# doch.net
KiCad netlist of a schematic drawn in EAGLE
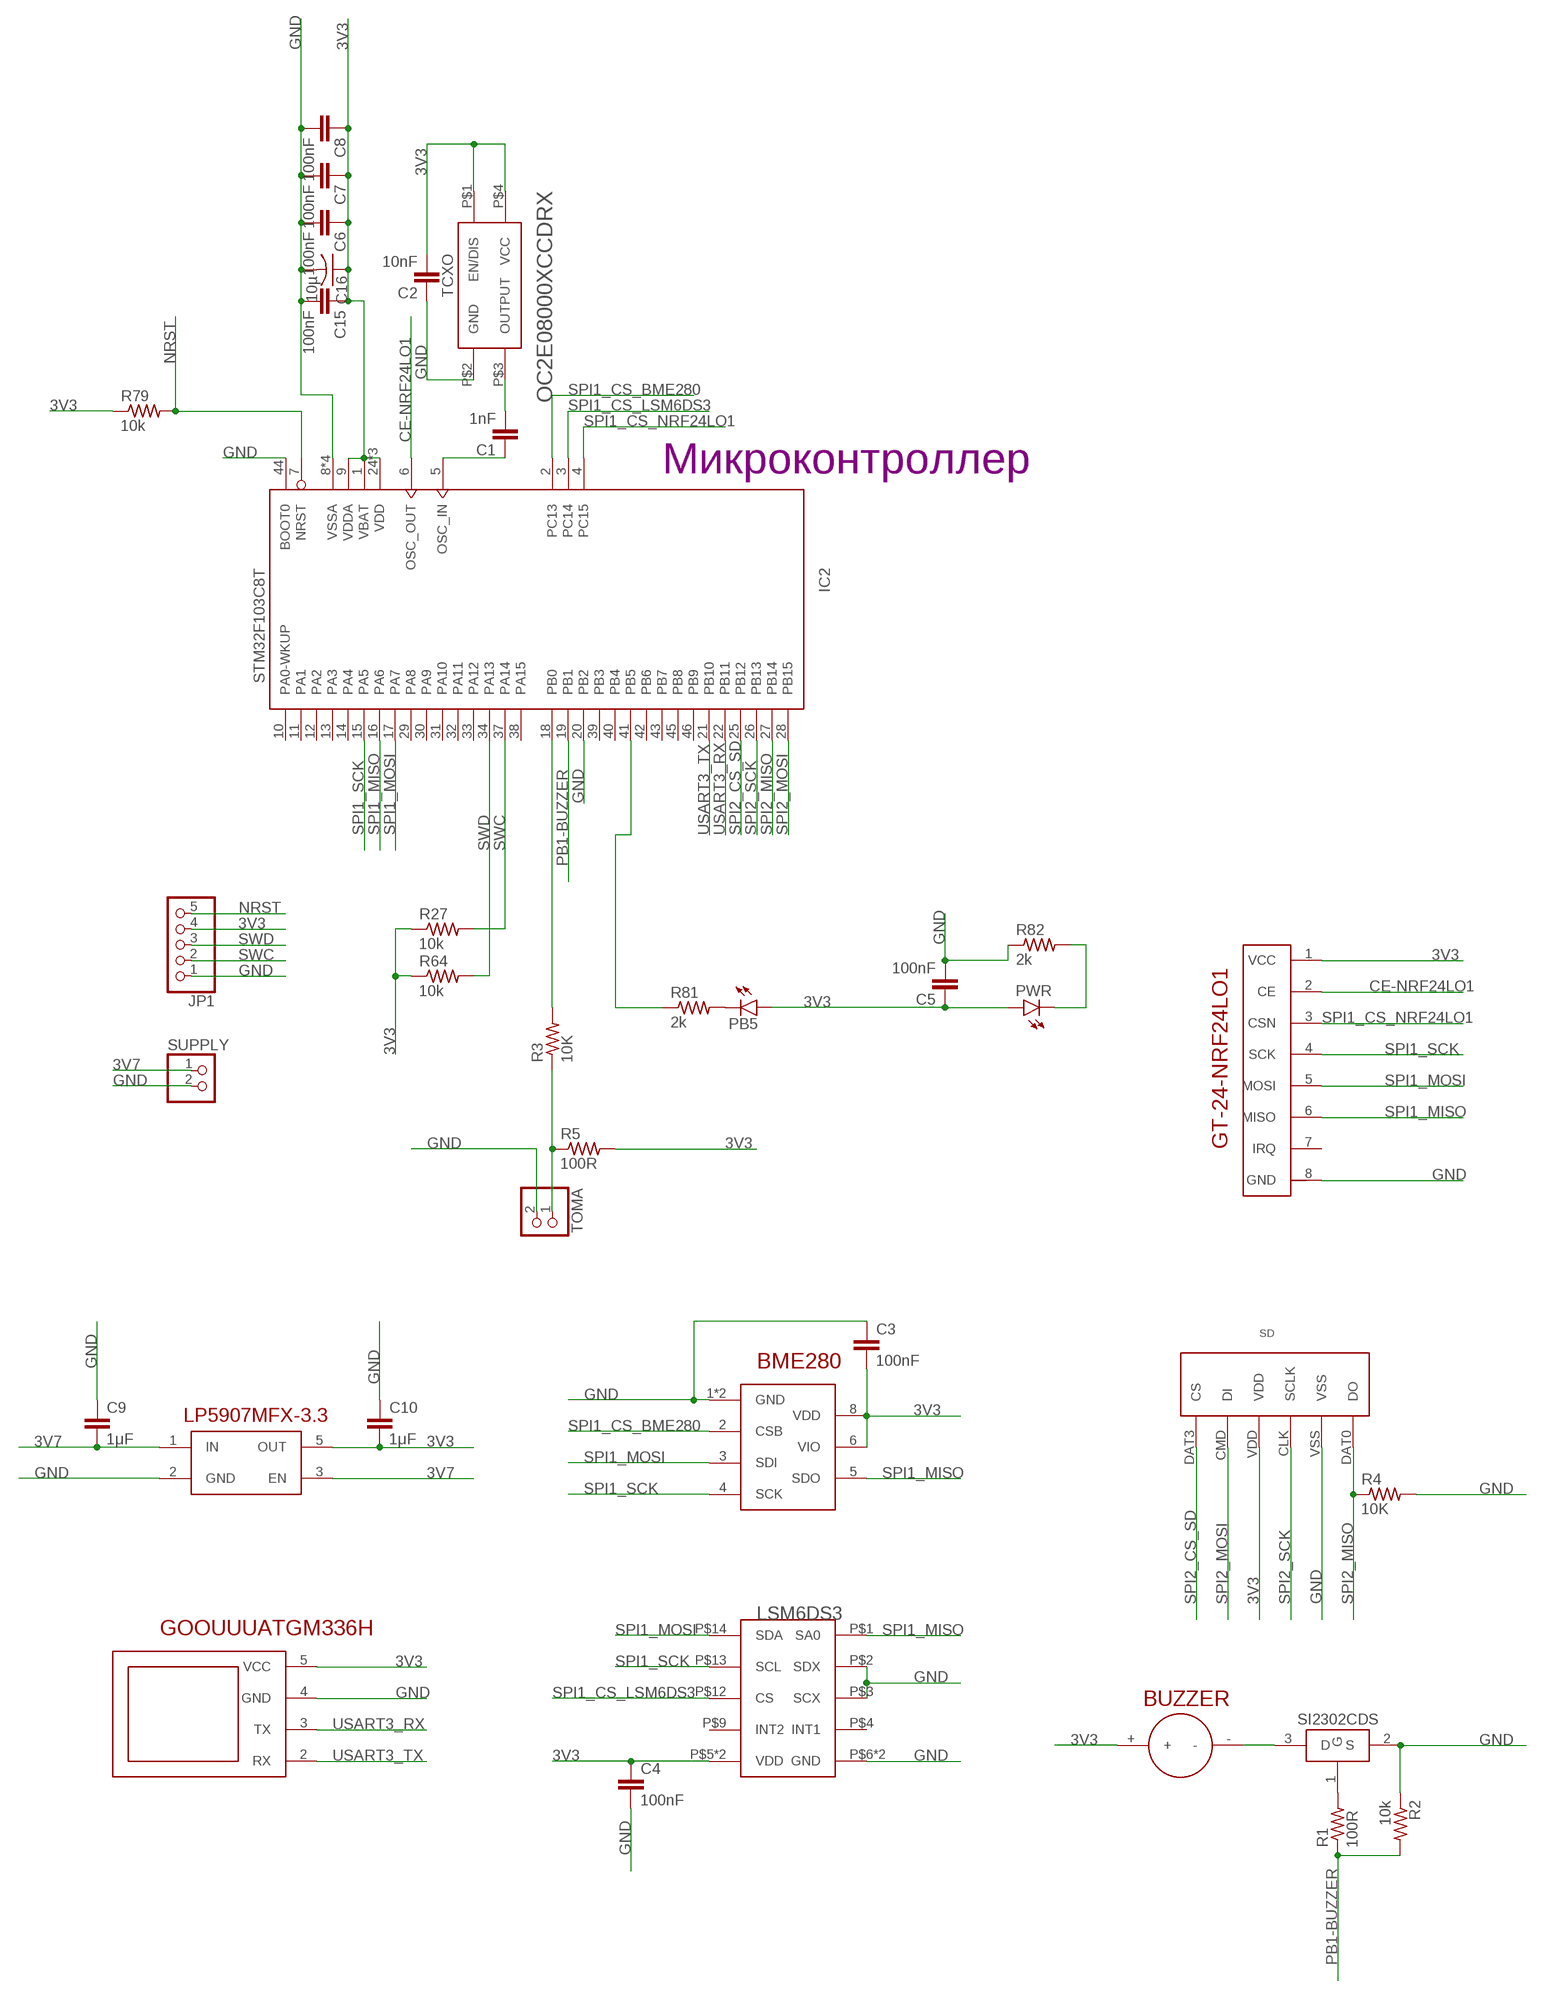
[diagram p0: schematic, sheet 1]

(export (version "E")
  (design (tool "Eeschema 10.0.6"))
  (components
    (comp (ref "BME280")
      (value "BME280CHIP")
      (footprint "eagle-import:BME280CHIP")
      (libsource (lib "eagle-import") (part "BME280CHIP"))
    )
    (comp (ref "BUZZER")
      (value "BUZZER")
      (footprint "eagle-import:BUZZER")
      (libsource (lib "eagle-import") (part "BUZZER"))
    )
    (comp (ref "C1")
      (value "1nF")
      (footprint "eagle-import:C0603")
      (libsource (lib "eagle-import") (part "C-EUC0603"))
    )
    (comp (ref "C2")
      (value "10nF")
      (footprint "eagle-import:C0603")
      (libsource (lib "eagle-import") (part "C-EUC0603"))
    )
    (comp (ref "C3")
      (value "100nF")
      (footprint "eagle-import:C0603")
      (libsource (lib "eagle-import") (part "C-EUC0603"))
    )
    (comp (ref "C4")
      (value "100nF")
      (footprint "eagle-import:C0603")
      (libsource (lib "eagle-import") (part "C-EUC0603"))
    )
    (comp (ref "C5")
      (value "100nF")
      (footprint "eagle-import:C0603")
      (libsource (lib "eagle-import") (part "C-EUC0603"))
    )
    (comp (ref "C6")
      (value "100nF")
      (footprint "eagle-import:C0603")
      (libsource (lib "eagle-import") (part "C-EUC0603"))
    )
    (comp (ref "C7")
      (value "100nF")
      (footprint "eagle-import:C0603")
      (libsource (lib "eagle-import") (part "C-EUC0603"))
    )
    (comp (ref "C8")
      (value "100nF")
      (footprint "eagle-import:C0603")
      (libsource (lib "eagle-import") (part "C-EUC0603"))
    )
    (comp (ref "C9")
      (value "1μF")
      (footprint "eagle-import:C0603")
      (libsource (lib "eagle-import") (part "C-EUC0603"))
    )
    (comp (ref "C10")
      (value "1μF")
      (footprint "eagle-import:C0603")
      (libsource (lib "eagle-import") (part "C-EUC0603"))
    )
    (comp (ref "C15")
      (value "100nF")
      (footprint "eagle-import:C0603")
      (libsource (lib "eagle-import") (part "C-EUC0603"))
    )
    (comp (ref "C16")
      (value "10µ")
      (footprint "eagle-import:C1206")
      (libsource (lib "eagle-import") (part "C-USC1206"))
    )
    (comp (ref "GOOUUUATGM336H")
      (value "GOOUUUATGM336H")
      (footprint "eagle-import:GOOUUUATGM336H")
      (libsource (lib "eagle-import") (part "GOOUUUATGM336H"))
    )
    (comp (ref "GT-24-NRF24LO1")
      (value "GT-24-NRF24LO1")
      (footprint "eagle-import:GT-24-NRF24LO1")
      (libsource (lib "eagle-import") (part "GT-24-NRF24LO1"))
    )
    (comp (ref "IC2")
      (value "STM32F103C8T")
      (footprint "eagle-import:LQFP48")
      (libsource (lib "eagle-import") (part "STM32F103CT8"))
    )
    (comp (ref "JP1")
      (value "PINHD-1X5")
      (footprint "eagle-import:1X05")
      (libsource (lib "eagle-import") (part "PINHD-1X5"))
    )
    (comp (ref "LP5907MFX-3.3")
      (value "LP5907MFX-3.3")
      (footprint "eagle-import:5PINSOT23")
      (libsource (lib "eagle-import") (part "LP5907MFX-3.3"))
    )
    (comp (ref "LSM6DS3")
      (value "LSM6DS3")
      (footprint "eagle-import:LGA-14")
      (libsource (lib "eagle-import") (part "LSM6DS3"))
    )
    (comp (ref "PB5")
      (value "LEDCHIPLED_0603")
      (footprint "eagle-import:CHIPLED_0603")
      (libsource (lib "eagle-import") (part "LEDCHIPLED_0603"))
    )
    (comp (ref "PWR")
      (value "LEDCHIPLED_0603")
      (footprint "eagle-import:CHIPLED_0603")
      (libsource (lib "eagle-import") (part "LEDCHIPLED_0603"))
    )
    (comp (ref "R1")
      (value "100R")
      (footprint "eagle-import:R0603")
      (libsource (lib "eagle-import") (part "R-US_R0603"))
    )
    (comp (ref "R2")
      (value "10k")
      (footprint "eagle-import:R0603")
      (libsource (lib "eagle-import") (part "R-US_R0603"))
    )
    (comp (ref "R3")
      (value "10K")
      (footprint "eagle-import:R0603")
      (libsource (lib "eagle-import") (part "R-US_R0603"))
    )
    (comp (ref "R4")
      (value "10K")
      (footprint "eagle-import:R0603")
      (libsource (lib "eagle-import") (part "R-US_R0603"))
    )
    (comp (ref "R5")
      (value "100R")
      (footprint "eagle-import:R0603")
      (libsource (lib "eagle-import") (part "R-US_R0603"))
    )
    (comp (ref "R27")
      (value "10k")
      (footprint "eagle-import:R0603")
      (libsource (lib "eagle-import") (part "resistor_R-US_R0603"))
    )
    (comp (ref "R64")
      (value "10k")
      (footprint "eagle-import:R0603")
      (libsource (lib "eagle-import") (part "resistor_R-US_R0603"))
    )
    (comp (ref "R79")
      (value "10k")
      (footprint "eagle-import:R0603")
      (libsource (lib "eagle-import") (part "resistor_R-US_R0603"))
    )
    (comp (ref "R81")
      (value "2k")
      (footprint "eagle-import:R0603")
      (libsource (lib "eagle-import") (part "resistor_R-US_R0603"))
    )
    (comp (ref "R82")
      (value "2k")
      (footprint "eagle-import:R0603")
      (libsource (lib "eagle-import") (part "resistor_R-US_R0603"))
    )
    (comp (ref "SD")
      (value "SD-SPI")
      (footprint "eagle-import:SD")
      (libsource (lib "eagle-import") (part "SD-SPI"))
    )
    (comp (ref "SUPPLY")
      (value "PINHD-1X2")
      (footprint "eagle-import:1X02")
      (libsource (lib "eagle-import") (part "PINHD-1X2"))
    )
    (comp (ref "TCXO")
      (value "OC2E08000XCCDRX")
      (footprint "eagle-import:OC2E08000XCCDRX")
      (libsource (lib "eagle-import") (part "OC2E08000XCCDRX"))
    )
    (comp (ref "TOMA")
      (value "PINHD-1X2/90")
      (footprint "eagle-import:1X02_90")
      (libsource (lib "eagle-import") (part "PINHD-1X2/90"))
    )
    (comp (ref "U$1")
      (value "SI2302CDS")
      (footprint "eagle-import:SOT23-3")
      (libsource (lib "eagle-import") (part "SI2302CDS"))
    )
  )
  (nets
    (net (code "1") (name "/3V3") (class "Default")
      (node (ref "BME280") (pin "6") (pinfunction "VIO_6") (pintype "bidirectional"))
      (node (ref "BME280") (pin "8") (pinfunction "VDD_8") (pintype "bidirectional"))
      (node (ref "BUZZER") (pin "+") (pinfunction "+_+") (pintype "bidirectional"))
      (node (ref "C10") (pin "2") (pinfunction "2_2") (pintype "passive"))
      (node (ref "C15") (pin "1") (pinfunction "1_1") (pintype "passive"))
      (node (ref "C16") (pin "1") (pinfunction "1_1") (pintype "passive"))
      (node (ref "C2") (pin "2") (pinfunction "2_2") (pintype "passive"))
      (node (ref "C3") (pin "2") (pinfunction "2_2") (pintype "passive"))
      (node (ref "C4") (pin "1") (pinfunction "1_1") (pintype "passive"))
      (node (ref "C5") (pin "1") (pinfunction "1_1") (pintype "passive"))
      (node (ref "C6") (pin "1") (pinfunction "1_1") (pintype "passive"))
      (node (ref "C7") (pin "1") (pinfunction "1_1") (pintype "passive"))
      (node (ref "C8") (pin "1") (pinfunction "1_1") (pintype "passive"))
      (node (ref "GOOUUUATGM336H") (pin "5") (pinfunction "VCC_5") (pintype "bidirectional"))
      (node (ref "GT-24-NRF24LO1") (pin "1") (pinfunction "VCC_1") (pintype "bidirectional"))
      (node (ref "IC2") (pin "1") (pinfunction "VBAT_1") (pintype "power_in"))
      (node (ref "IC2") (pin "24") (pinfunction "VDD_24") (pintype "bidirectional"))
      (node (ref "IC2") (pin "36") (pinfunction "VDD_36") (pintype "bidirectional"))
      (node (ref "IC2") (pin "48") (pinfunction "VDD_48") (pintype "bidirectional"))
      (node (ref "IC2") (pin "9") (pinfunction "VDDA_9") (pintype "power_in"))
      (node (ref "JP1") (pin "4") (pinfunction "4_4") (pintype "passive"))
      (node (ref "LP5907MFX-3.3") (pin "5") (pinfunction "OUT_5") (pintype "bidirectional"))
      (node (ref "LSM6DS3") (pin "P$5") (pinfunction "VDD_P$5") (pintype "bidirectional"))
      (node (ref "LSM6DS3") (pin "P$8") (pinfunction "VDD_P$8") (pintype "bidirectional"))
      (node (ref "PB5") (pin "A") (pinfunction "A_A") (pintype "passive"))
      (node (ref "PWR") (pin "A") (pinfunction "A_A") (pintype "passive"))
      (node (ref "R27") (pin "1") (pinfunction "1_1") (pintype "passive"))
      (node (ref "R5") (pin "2") (pinfunction "2_2") (pintype "passive"))
      (node (ref "R64") (pin "1") (pinfunction "1_1") (pintype "passive"))
      (node (ref "R79") (pin "1") (pinfunction "1_1") (pintype "passive"))
      (node (ref "SD") (pin "VDD") (pinfunction "VDD_VDD") (pintype "bidirectional"))
      (node (ref "TCXO") (pin "P$1") (pinfunction "EN/DIS_P$1") (pintype "bidirectional"))
      (node (ref "TCXO") (pin "P$4") (pinfunction "VCC_P$4") (pintype "bidirectional"))
    )
    (net (code "2") (name "/3V7") (class "Default")
      (node (ref "C9") (pin "2") (pinfunction "2_2") (pintype "passive"))
      (node (ref "LP5907MFX-3.3") (pin "1") (pinfunction "IN_1") (pintype "bidirectional"))
      (node (ref "LP5907MFX-3.3") (pin "3") (pinfunction "EN_3") (pintype "bidirectional"))
      (node (ref "SUPPLY") (pin "1") (pinfunction "1_1") (pintype "passive"))
    )
    (net (code "3") (name "/CE-NRF24LO1") (class "Default")
      (node (ref "GT-24-NRF24LO1") (pin "2") (pinfunction "CE_2") (pintype "bidirectional"))
      (node (ref "IC2") (pin "6") (pinfunction "OSC_OUT_6") (pintype "bidirectional"))
    )
    (net (code "4") (name "/GND") (class "Default")
      (node (ref "BME280") (pin "1") (pinfunction "GND_1") (pintype "bidirectional"))
      (node (ref "BME280") (pin "7") (pinfunction "GND_7") (pintype "bidirectional"))
      (node (ref "C10") (pin "1") (pinfunction "1_1") (pintype "passive"))
      (node (ref "C15") (pin "2") (pinfunction "2_2") (pintype "passive"))
      (node (ref "C16") (pin "2") (pinfunction "2_2") (pintype "passive"))
      (node (ref "C2") (pin "1") (pinfunction "1_1") (pintype "passive"))
      (node (ref "C3") (pin "1") (pinfunction "1_1") (pintype "passive"))
      (node (ref "C4") (pin "2") (pinfunction "2_2") (pintype "passive"))
      (node (ref "C5") (pin "2") (pinfunction "2_2") (pintype "passive"))
      (node (ref "C6") (pin "2") (pinfunction "2_2") (pintype "passive"))
      (node (ref "C7") (pin "2") (pinfunction "2_2") (pintype "passive"))
      (node (ref "C8") (pin "2") (pinfunction "2_2") (pintype "passive"))
      (node (ref "C9") (pin "1") (pinfunction "1_1") (pintype "passive"))
      (node (ref "GOOUUUATGM336H") (pin "4") (pinfunction "GND_4") (pintype "bidirectional"))
      (node (ref "GT-24-NRF24LO1") (pin "8") (pinfunction "GND_8") (pintype "bidirectional"))
      (node (ref "IC2") (pin "20") (pinfunction "PB2_20") (pintype "bidirectional"))
      (node (ref "IC2") (pin "23") (pinfunction "VSSA_23") (pintype "power_in"))
      (node (ref "IC2") (pin "35") (pinfunction "VSSA_35") (pintype "power_in"))
      (node (ref "IC2") (pin "44") (pinfunction "BOOT0_44") (pintype "input"))
      (node (ref "IC2") (pin "47") (pinfunction "VSSA_47") (pintype "power_in"))
      (node (ref "IC2") (pin "8") (pinfunction "VSSA_8") (pintype "power_in"))
      (node (ref "JP1") (pin "1") (pinfunction "1_1") (pintype "passive"))
      (node (ref "LP5907MFX-3.3") (pin "2") (pinfunction "GND_2") (pintype "bidirectional"))
      (node (ref "LSM6DS3") (pin "P$2") (pinfunction "SDX_P$2") (pintype "bidirectional"))
      (node (ref "LSM6DS3") (pin "P$3") (pinfunction "SCX_P$3") (pintype "bidirectional"))
      (node (ref "LSM6DS3") (pin "P$6") (pinfunction "GND_P$6") (pintype "bidirectional"))
      (node (ref "LSM6DS3") (pin "P$7") (pinfunction "GND_P$7") (pintype "bidirectional"))
      (node (ref "R2") (pin "1") (pinfunction "1_1") (pintype "passive"))
      (node (ref "R4") (pin "2") (pinfunction "2_2") (pintype "passive"))
      (node (ref "R82") (pin "1") (pinfunction "1_1") (pintype "passive"))
      (node (ref "SD") (pin "VSS") (pinfunction "VSS_VSS") (pintype "bidirectional"))
      (node (ref "SUPPLY") (pin "2") (pinfunction "2_2") (pintype "passive"))
      (node (ref "TCXO") (pin "P$2") (pinfunction "GND_P$2") (pintype "bidirectional"))
      (node (ref "TOMA") (pin "2") (pinfunction "2_2") (pintype "passive"))
      (node (ref "U$1") (pin "2") (pinfunction "S_2") (pintype "bidirectional"))
    )
    (net (code "5") (name "/NRST") (class "Default")
      (node (ref "IC2") (pin "7") (pinfunction "NRST_7") (pintype "bidirectional"))
      (node (ref "JP1") (pin "5") (pinfunction "5_5") (pintype "passive"))
      (node (ref "R79") (pin "2") (pinfunction "2_2") (pintype "passive"))
    )
    (net (code "6") (name "/PB1-BUZZER") (class "Default")
      (node (ref "IC2") (pin "19") (pinfunction "PB1_19") (pintype "bidirectional"))
      (node (ref "R1") (pin "1") (pinfunction "1_1") (pintype "passive"))
      (node (ref "R2") (pin "2") (pinfunction "2_2") (pintype "passive"))
    )
    (net (code "7") (name "/SPI1_CS_BME280") (class "Default")
      (node (ref "BME280") (pin "2") (pinfunction "CSB_2") (pintype "bidirectional"))
      (node (ref "IC2") (pin "2") (pinfunction "PC13_2") (pintype "bidirectional"))
    )
    (net (code "8") (name "/SPI1_CS_LSM6DS3") (class "Default")
      (node (ref "IC2") (pin "3") (pinfunction "PC14_3") (pintype "bidirectional"))
      (node (ref "LSM6DS3") (pin "P$12") (pinfunction "CS_P$12") (pintype "bidirectional"))
    )
    (net (code "9") (name "/SPI1_CS_NRF24LO1") (class "Default")
      (node (ref "GT-24-NRF24LO1") (pin "3") (pinfunction "CSN_3") (pintype "bidirectional"))
      (node (ref "IC2") (pin "4") (pinfunction "PC15_4") (pintype "bidirectional"))
    )
    (net (code "10") (name "/SPI1_MISO") (class "Default")
      (node (ref "BME280") (pin "5") (pinfunction "SDO_5") (pintype "bidirectional"))
      (node (ref "GT-24-NRF24LO1") (pin "6") (pinfunction "MISO_6") (pintype "bidirectional"))
      (node (ref "IC2") (pin "16") (pinfunction "PA6_16") (pintype "bidirectional"))
      (node (ref "LSM6DS3") (pin "P$1") (pinfunction "SA0_P$1") (pintype "bidirectional"))
    )
    (net (code "11") (name "/SPI1_MOSI") (class "Default")
      (node (ref "BME280") (pin "3") (pinfunction "SDI_3") (pintype "bidirectional"))
      (node (ref "GT-24-NRF24LO1") (pin "5") (pinfunction "MOSI_5") (pintype "bidirectional"))
      (node (ref "IC2") (pin "17") (pinfunction "PA7_17") (pintype "bidirectional"))
      (node (ref "LSM6DS3") (pin "P$14") (pinfunction "SDA_P$14") (pintype "bidirectional"))
    )
    (net (code "12") (name "/SPI1_SCK") (class "Default")
      (node (ref "BME280") (pin "4") (pinfunction "SCK_4") (pintype "bidirectional"))
      (node (ref "GT-24-NRF24LO1") (pin "4") (pinfunction "SCK_4") (pintype "bidirectional"))
      (node (ref "IC2") (pin "15") (pinfunction "PA5_15") (pintype "bidirectional"))
      (node (ref "LSM6DS3") (pin "P$13") (pinfunction "SCL_P$13") (pintype "bidirectional"))
    )
    (net (code "13") (name "/SPI2_CS_SD") (class "Default")
      (node (ref "IC2") (pin "25") (pinfunction "PB12_25") (pintype "bidirectional"))
      (node (ref "SD") (pin "DAT3") (pinfunction "CS_DAT3") (pintype "bidirectional"))
    )
    (net (code "14") (name "/SPI2_MISO") (class "Default")
      (node (ref "IC2") (pin "27") (pinfunction "PB14_27") (pintype "bidirectional"))
      (node (ref "R4") (pin "1") (pinfunction "1_1") (pintype "passive"))
      (node (ref "SD") (pin "DAT0") (pinfunction "DO_DAT0") (pintype "bidirectional"))
    )
    (net (code "15") (name "/SPI2_MOSI") (class "Default")
      (node (ref "IC2") (pin "28") (pinfunction "PB15_28") (pintype "bidirectional"))
      (node (ref "SD") (pin "CMD") (pinfunction "DI_CMD") (pintype "bidirectional"))
    )
    (net (code "16") (name "/SPI2_SCK") (class "Default")
      (node (ref "IC2") (pin "26") (pinfunction "PB13_26") (pintype "bidirectional"))
      (node (ref "SD") (pin "CLK") (pinfunction "SCLK_CLK") (pintype "bidirectional"))
    )
    (net (code "17") (name "/SWC") (class "Default")
      (node (ref "IC2") (pin "37") (pinfunction "PA14_37") (pintype "bidirectional"))
      (node (ref "JP1") (pin "2") (pinfunction "2_2") (pintype "passive"))
      (node (ref "R27") (pin "2") (pinfunction "2_2") (pintype "passive"))
    )
    (net (code "18") (name "/SWD") (class "Default")
      (node (ref "IC2") (pin "34") (pinfunction "PA13_34") (pintype "bidirectional"))
      (node (ref "JP1") (pin "3") (pinfunction "3_3") (pintype "passive"))
      (node (ref "R64") (pin "2") (pinfunction "2_2") (pintype "passive"))
    )
    (net (code "19") (name "/USART3_RX") (class "Default")
      (node (ref "GOOUUUATGM336H") (pin "3") (pinfunction "TX_3") (pintype "bidirectional"))
      (node (ref "IC2") (pin "22") (pinfunction "PB11_22") (pintype "bidirectional"))
    )
    (net (code "20") (name "/USART3_TX") (class "Default")
      (node (ref "GOOUUUATGM336H") (pin "2") (pinfunction "RX_2") (pintype "bidirectional"))
      (node (ref "IC2") (pin "21") (pinfunction "PB10_21") (pintype "bidirectional"))
    )
    (net (code "21") (name "Net-(IC2-OSC_IN)") (class "Default")
      (node (ref "C1") (pin "1") (pinfunction "1_1") (pintype "passive"))
      (node (ref "IC2") (pin "5") (pinfunction "OSC_IN_5") (pintype "bidirectional"))
    )
    (net (code "22") (name "Net-(IC2-PB0)") (class "Default")
      (node (ref "IC2") (pin "18") (pinfunction "PB0_18") (pintype "bidirectional"))
      (node (ref "R3") (pin "2") (pinfunction "2_2") (pintype "passive"))
    )
    (net (code "23") (name "Net-(IC2-PB5)") (class "Default")
      (node (ref "IC2") (pin "41") (pinfunction "PB5_41") (pintype "bidirectional"))
      (node (ref "R81") (pin "1") (pinfunction "1_1") (pintype "passive"))
    )
    (net (code "24") (name "Net-(PB5-PadC)") (class "Default")
      (node (ref "PB5") (pin "C") (pinfunction "C_C") (pintype "passive"))
      (node (ref "R81") (pin "2") (pinfunction "2_2") (pintype "passive"))
    )
    (net (code "25") (name "Net-(PWR-PadC)") (class "Default")
      (node (ref "PWR") (pin "C") (pinfunction "C_C") (pintype "passive"))
      (node (ref "R82") (pin "2") (pinfunction "2_2") (pintype "passive"))
    )
    (net (code "26") (name "Net-(R3-Pad1)") (class "Default")
      (node (ref "R3") (pin "1") (pinfunction "1_1") (pintype "passive"))
      (node (ref "R5") (pin "1") (pinfunction "1_1") (pintype "passive"))
      (node (ref "TOMA") (pin "1") (pinfunction "1_1") (pintype "passive"))
    )
    (net (code "27") (name "Net-(TCXO-OUTPUT)") (class "Default")
      (node (ref "C1") (pin "2") (pinfunction "2_2") (pintype "passive"))
      (node (ref "TCXO") (pin "P$3") (pinfunction "OUTPUT_P$3") (pintype "bidirectional"))
    )
    (net (code "28") (name "Net-(U$1-D)") (class "Default")
      (node (ref "BUZZER") (pin "-") (pinfunction "-_-") (pintype "bidirectional"))
      (node (ref "U$1") (pin "3") (pinfunction "D_3") (pintype "bidirectional"))
    )
    (net (code "29") (name "Net-(U$1-G)") (class "Default")
      (node (ref "R1") (pin "2") (pinfunction "2_2") (pintype "passive"))
      (node (ref "U$1") (pin "1") (pinfunction "G_1") (pintype "bidirectional"))
    )
    (net (code "30") (name "unconnected-(GT-24-NRF24LO1-IRQ-Pad7)") (class "Default")
      (node (ref "GT-24-NRF24LO1") (pin "7") (pinfunction "IRQ_7") (pintype "bidirectional"))
    )
    (net (code "31") (name "unconnected-(IC2-PA0-WKUP-Pad10)") (class "Default")
      (node (ref "IC2") (pin "10") (pinfunction "PA0-WKUP_10") (pintype "bidirectional"))
    )
    (net (code "32") (name "unconnected-(IC2-PA1-Pad11)") (class "Default")
      (node (ref "IC2") (pin "11") (pinfunction "PA1_11") (pintype "bidirectional"))
    )
    (net (code "33") (name "unconnected-(IC2-PA2-Pad12)") (class "Default")
      (node (ref "IC2") (pin "12") (pinfunction "PA2_12") (pintype "bidirectional"))
    )
    (net (code "34") (name "unconnected-(IC2-PA3-Pad13)") (class "Default")
      (node (ref "IC2") (pin "13") (pinfunction "PA3_13") (pintype "bidirectional"))
    )
    (net (code "35") (name "unconnected-(IC2-PA4-Pad14)") (class "Default")
      (node (ref "IC2") (pin "14") (pinfunction "PA4_14") (pintype "bidirectional"))
    )
    (net (code "36") (name "unconnected-(IC2-PA8-Pad29)") (class "Default")
      (node (ref "IC2") (pin "29") (pinfunction "PA8_29") (pintype "bidirectional"))
    )
    (net (code "37") (name "unconnected-(IC2-PA9-Pad30)") (class "Default")
      (node (ref "IC2") (pin "30") (pinfunction "PA9_30") (pintype "bidirectional"))
    )
    (net (code "38") (name "unconnected-(IC2-PA10-Pad31)") (class "Default")
      (node (ref "IC2") (pin "31") (pinfunction "PA10_31") (pintype "bidirectional"))
    )
    (net (code "39") (name "unconnected-(IC2-PA11-Pad32)") (class "Default")
      (node (ref "IC2") (pin "32") (pinfunction "PA11_32") (pintype "bidirectional"))
    )
    (net (code "40") (name "unconnected-(IC2-PA12-Pad33)") (class "Default")
      (node (ref "IC2") (pin "33") (pinfunction "PA12_33") (pintype "bidirectional"))
    )
    (net (code "41") (name "unconnected-(IC2-PA15-Pad38)") (class "Default")
      (node (ref "IC2") (pin "38") (pinfunction "PA15_38") (pintype "bidirectional"))
    )
    (net (code "42") (name "unconnected-(IC2-PB3-Pad39)") (class "Default")
      (node (ref "IC2") (pin "39") (pinfunction "PB3_39") (pintype "bidirectional"))
    )
    (net (code "43") (name "unconnected-(IC2-PB4-Pad40)") (class "Default")
      (node (ref "IC2") (pin "40") (pinfunction "PB4_40") (pintype "bidirectional"))
    )
    (net (code "44") (name "unconnected-(IC2-PB6-Pad42)") (class "Default")
      (node (ref "IC2") (pin "42") (pinfunction "PB6_42") (pintype "bidirectional"))
    )
    (net (code "45") (name "unconnected-(IC2-PB7-Pad43)") (class "Default")
      (node (ref "IC2") (pin "43") (pinfunction "PB7_43") (pintype "bidirectional"))
    )
    (net (code "46") (name "unconnected-(IC2-PB8-Pad45)") (class "Default")
      (node (ref "IC2") (pin "45") (pinfunction "PB8_45") (pintype "bidirectional"))
    )
    (net (code "47") (name "unconnected-(IC2-PB9-Pad46)") (class "Default")
      (node (ref "IC2") (pin "46") (pinfunction "PB9_46") (pintype "bidirectional"))
    )
    (net (code "48") (name "unconnected-(LSM6DS3-INT1-PadP$4)") (class "Default")
      (node (ref "LSM6DS3") (pin "P$4") (pinfunction "INT1_P$4") (pintype "bidirectional"))
    )
    (net (code "49") (name "unconnected-(LSM6DS3-INT2-PadP$9)") (class "Default")
      (node (ref "LSM6DS3") (pin "P$9") (pinfunction "INT2_P$9") (pintype "bidirectional"))
    )
  )
)
